# hall_sensor.net
KiCad netlist of a schematic drawn in Altium Designer
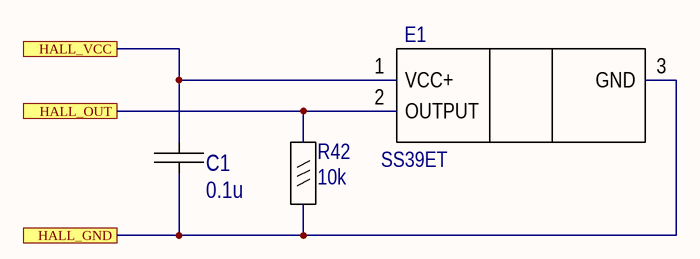
[diagram p0: hall_sensor.SchDoc]

(export (version "E")
  (design (tool "Eeschema 10.0.6"))
  (components
    (comp (ref "C1")
      (value "0.1u")
      (footprint "C0603_IPC")
      (description "0.1uF ±10% 50V Ceramic Capacitor X7R 0603 (1608 Metric)")
      (fields (field (name "PARTNUMBER") "0.1u 50V") (field (name "MPN") "CL10B104KB8NNND"))
      (libsource (lib "DB_res_cap_ind") (part "C0603_GOST"))
    )
    (comp (ref "E1")
      (value "SS39ET")
      (footprint "SOT-23")
      (description "Hall Effect Sensor Single Axis SOT-23")
      (libsource (lib "DB_the_rest") (part "SS39ET"))
    )
    (comp (ref "R42")
      (value "10k")
      (footprint "R0603")
      (description "10 kOhms ±5% 0.1W, 1/10W Chip Resistor 0603 (1608 Metric) Moisture Resistant Thick Film")
      (fields (field (name "MPN") "RC0603JR-0710kL") (field (name "TOLERANCE") "5%"))
      (libsource (lib "DB_res_cap_ind") (part "R0603"))
    )
  )
  (nets
    (net (code "1") (name "/HALL_GND") (class "Default")
      (node (ref "C1") (pin "2") (pinfunction "2_2") (pintype "passive"))
      (node (ref "E1") (pin "3") (pinfunction "GND_3") (pintype "passive"))
      (node (ref "R42") (pin "1") (pinfunction "1_1") (pintype "passive"))
    )
    (net (code "2") (name "/HALL_OUT") (class "Default")
      (node (ref "E1") (pin "2") (pinfunction "OUTPUT_2") (pintype "passive"))
      (node (ref "R42") (pin "2") (pinfunction "2_2") (pintype "passive"))
    )
    (net (code "3") (name "/HALL_VCC") (class "Default")
      (node (ref "C1") (pin "1") (pinfunction "1_1") (pintype "passive"))
      (node (ref "E1") (pin "1") (pinfunction "VCC+_1") (pintype "passive"))
    )
  )
)
